# ADDINBRD_V1.net
KiCad netlist of a schematic drawn in EAGLE
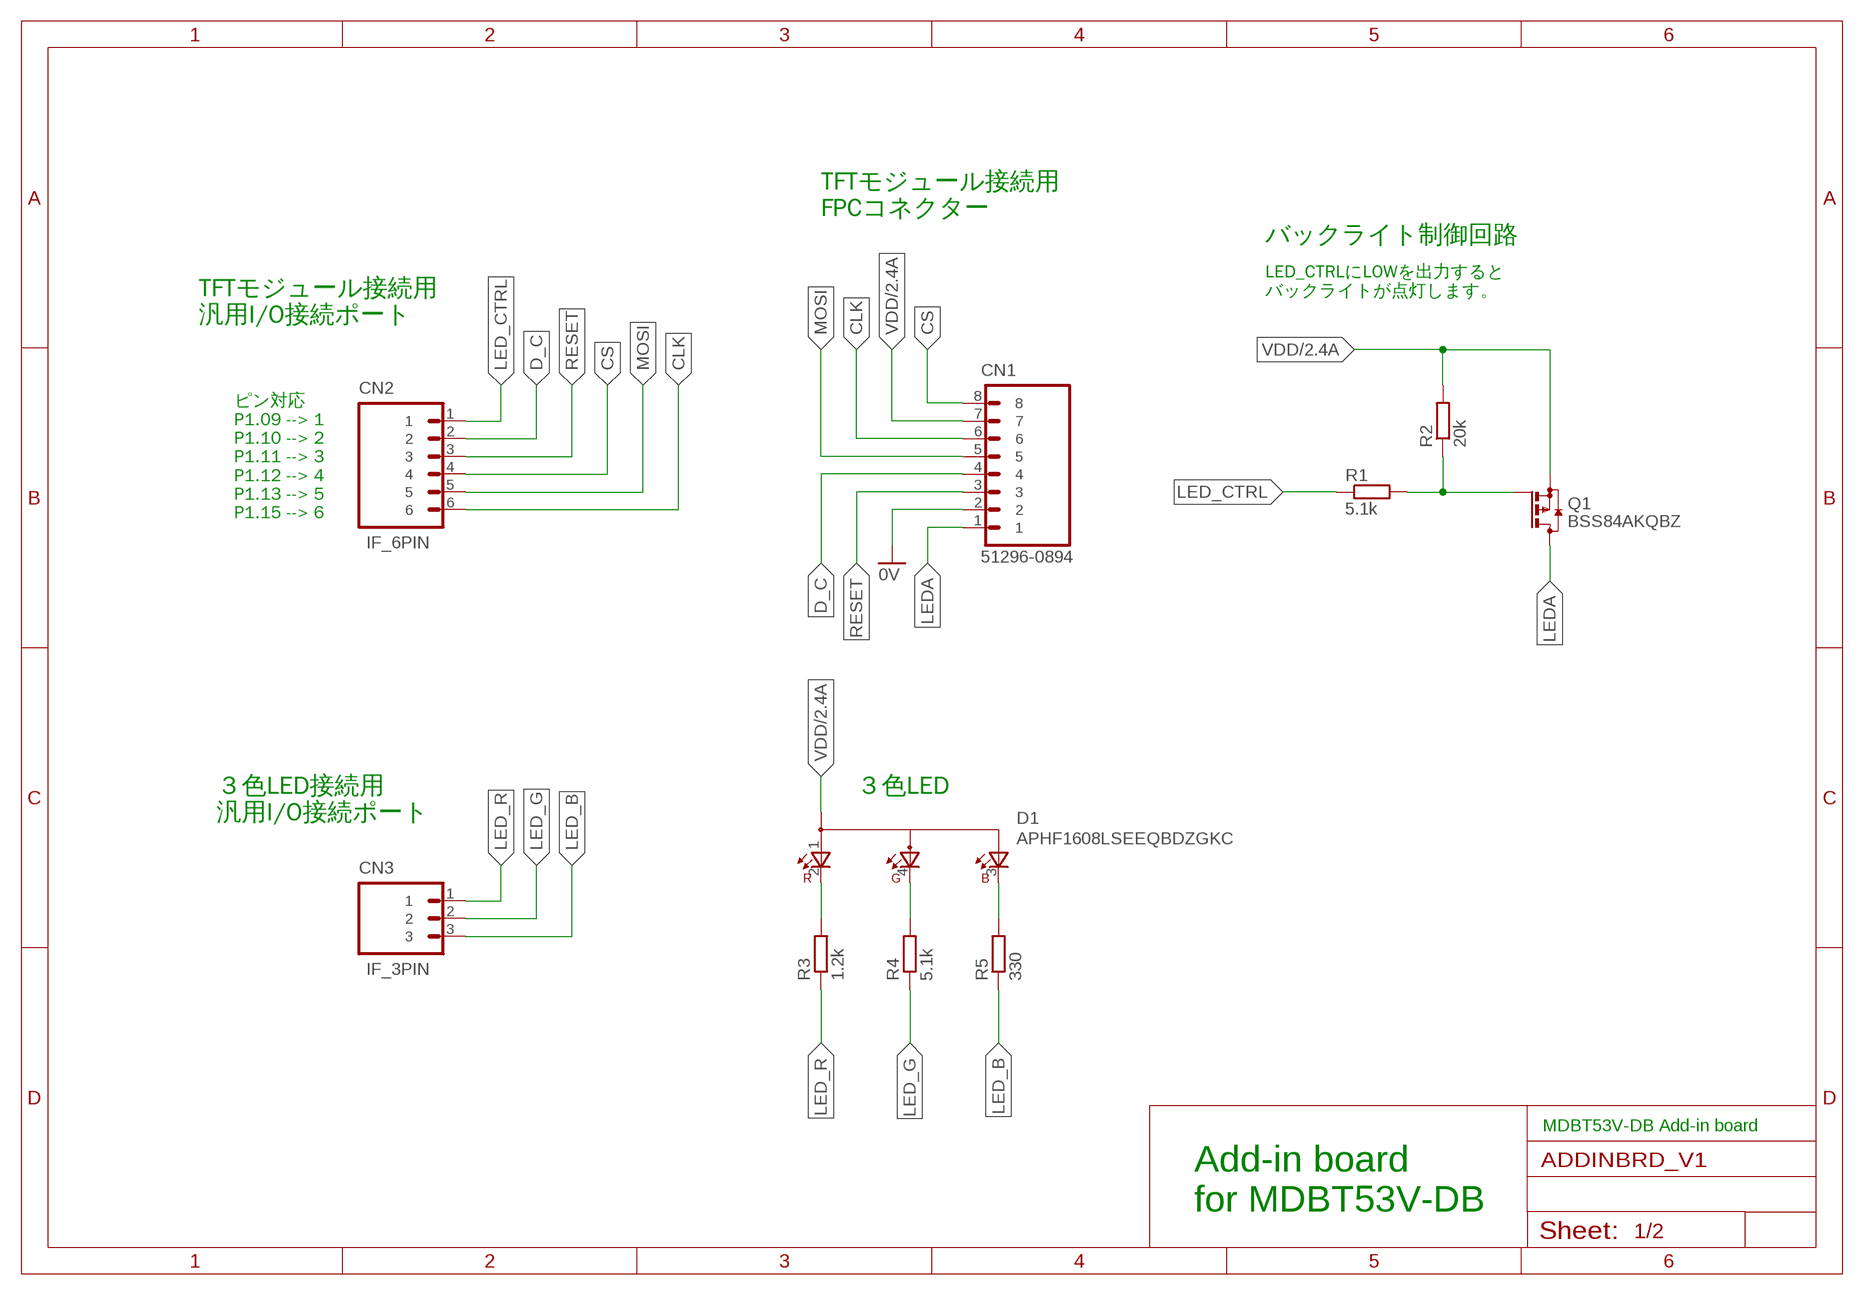
[diagram p0: schematic, sheet 1]
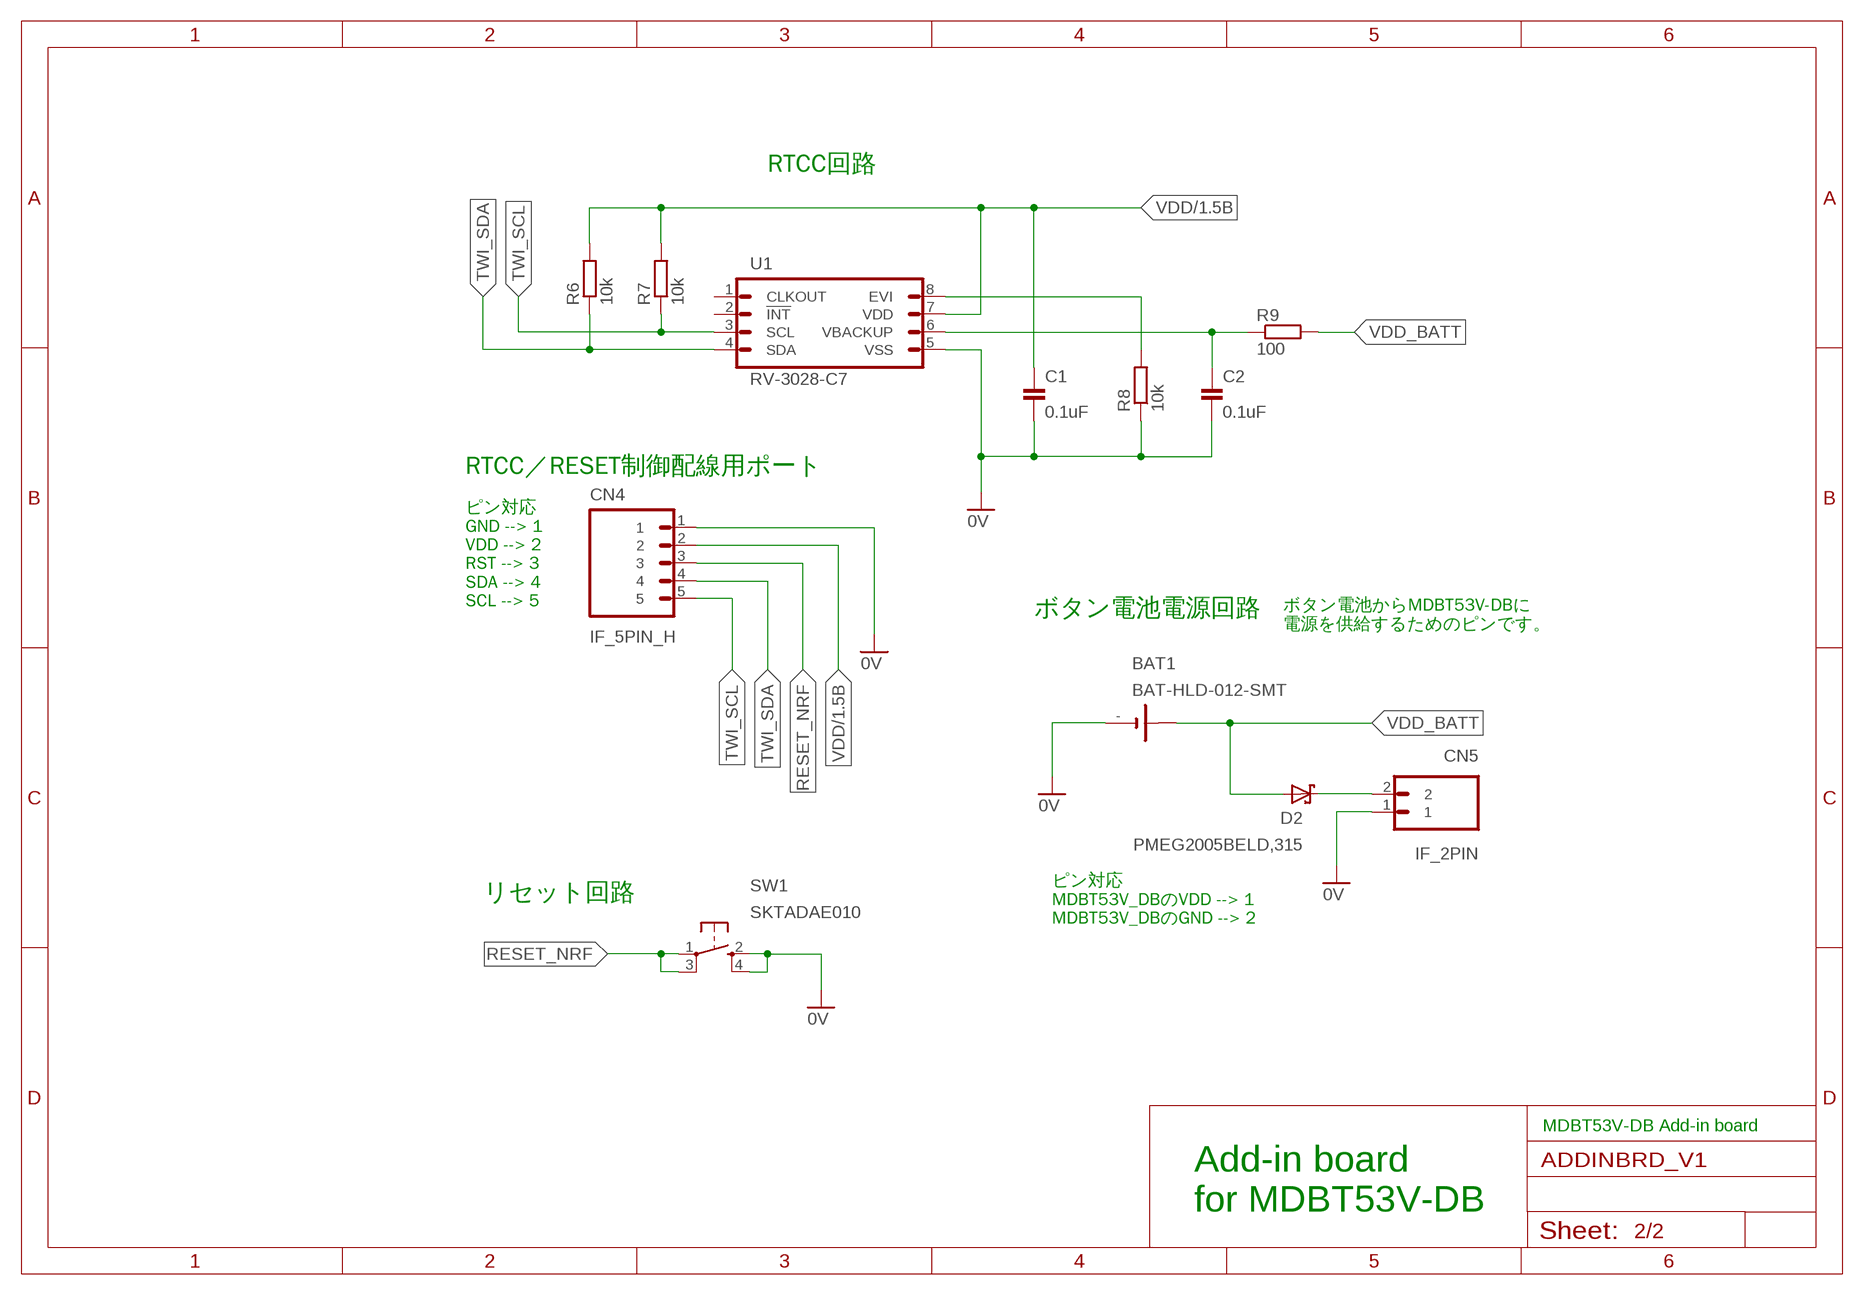
[diagram p1: schematic, sheet 2]

(export (version "E")
  (design (tool "Eeschema 10.0.6"))
  (components
    (comp (ref "CN1")
      (value "51296-0894")
      (footprint "eagle-import:51296-0894")
      (libsource (lib "eagle-import") (part "51296-0894"))
    )
    (comp (ref "CN2")
      (value "IF_6PIN")
      (footprint "eagle-import:HEADER_6PIN")
      (libsource (lib "eagle-import") (part "IF_6PIN"))
    )
    (comp (ref "CN3")
      (value "IF_3PIN")
      (footprint "eagle-import:HEADER_3PIN")
      (libsource (lib "eagle-import") (part "IF_3PIN"))
    )
    (comp (ref "D1")
      (value "APHF1608LSEEQBDZGKC")
      (footprint "eagle-import:APHF1608LSEEQBDZGKC")
      (libsource (lib "eagle-import") (part "APHF1608LSEEQBDZGKC"))
    )
    (comp (ref "Q1")
      (value "BSS84AKQBZ")
      (footprint "eagle-import:BSS84AKQB")
      (libsource (lib "eagle-import") (part "BSS84AKQBZ"))
    )
    (comp (ref "R1")
      (value "5.1k")
      (footprint "eagle-import:R0402N")
      (libsource (lib "eagle-import") (part "RESISTOR_0402N"))
    )
    (comp (ref "R2")
      (value "20k")
      (footprint "eagle-import:R0402N")
      (libsource (lib "eagle-import") (part "RESISTOR_0402N"))
    )
    (comp (ref "R3")
      (value "1.2k")
      (footprint "eagle-import:R0402N")
      (libsource (lib "eagle-import") (part "RESISTOR_0402N"))
    )
    (comp (ref "R4")
      (value "5.1k")
      (footprint "eagle-import:R0402N")
      (libsource (lib "eagle-import") (part "RESISTOR_0402N"))
    )
    (comp (ref "R5")
      (value "330")
      (footprint "eagle-import:R0402N")
      (libsource (lib "eagle-import") (part "RESISTOR_0402N"))
    )
    (comp (ref "BAT1")
      (value "BAT-HLD-012-SMT")
      (footprint "eagle-import:BAT-HLD-012-SMT")
      (libsource (lib "eagle-import") (part "BAT-HLD-012-SMT"))
    )
    (comp (ref "C1")
      (value "0.1uF")
      (footprint "eagle-import:C0402N")
      (libsource (lib "eagle-import") (part "CAP_0402N"))
    )
    (comp (ref "C2")
      (value "0.1uF")
      (footprint "eagle-import:C0402N")
      (libsource (lib "eagle-import") (part "CAP_0402N"))
    )
    (comp (ref "CN4")
      (value "IF_5PIN_H")
      (footprint "eagle-import:HEADER_5PIN")
      (libsource (lib "eagle-import") (part "IF_5PIN_H"))
    )
    (comp (ref "CN5")
      (value "IF_2PIN")
      (footprint "eagle-import:HEADER_2PIN")
      (libsource (lib "eagle-import") (part "IF_2PIN"))
    )
    (comp (ref "D2")
      (value "PMEG2005BELD,315")
      (footprint "eagle-import:DFN1006D-2")
      (libsource (lib "eagle-import") (part "PMEG2005BELD,315"))
    )
    (comp (ref "R6")
      (value "10k")
      (footprint "eagle-import:R0402N")
      (libsource (lib "eagle-import") (part "RESISTOR_0402N"))
    )
    (comp (ref "R7")
      (value "10k")
      (footprint "eagle-import:R0402N")
      (libsource (lib "eagle-import") (part "RESISTOR_0402N"))
    )
    (comp (ref "R8")
      (value "10k")
      (footprint "eagle-import:R0402N")
      (libsource (lib "eagle-import") (part "RESISTOR_0402N"))
    )
    (comp (ref "R9")
      (value "100")
      (footprint "eagle-import:R0402N")
      (libsource (lib "eagle-import") (part "RESISTOR_0402N"))
    )
    (comp (ref "SW1")
      (value "SKTADAE010")
      (footprint "eagle-import:SKTADAE010")
      (libsource (lib "eagle-import") (part "SKTADAE010"))
    )
    (comp (ref "U1")
      (value "RV-3028-C7")
      (footprint "eagle-import:SON-8")
      (libsource (lib "eagle-import") (part "RV-3028-C7"))
    )
  )
  (nets
    (net (code "1") (name "0V") (class "Default")
      (node (ref "BAT1") (pin "-") (pinfunction "-_-") (pintype "passive"))
      (node (ref "C1") (pin "2") (pinfunction "2_2") (pintype "passive"))
      (node (ref "C2") (pin "2") (pinfunction "2_2") (pintype "passive"))
      (node (ref "CN1") (pin "2") (pinfunction "2_2") (pintype "passive"))
      (node (ref "CN4") (pin "1") (pinfunction "1_1") (pintype "passive"))
      (node (ref "CN5") (pin "1") (pinfunction "1_1") (pintype "passive"))
      (node (ref "R8") (pin "1") (pinfunction "1_1") (pintype "passive"))
      (node (ref "SW1") (pin "2") (pinfunction "S_2") (pintype "passive"))
      (node (ref "SW1") (pin "4") (pinfunction "S1_4") (pintype "passive"))
      (node (ref "U1") (pin "5") (pinfunction "VSS_5") (pintype "passive"))
    )
    (net (code "2") (name "CLK") (class "Default")
      (node (ref "CN1") (pin "6") (pinfunction "6_6") (pintype "passive"))
      (node (ref "CN2") (pin "6") (pinfunction "6_6") (pintype "passive"))
    )
    (net (code "3") (name "CS") (class "Default")
      (node (ref "CN1") (pin "8") (pinfunction "8_8") (pintype "passive"))
      (node (ref "CN2") (pin "4") (pinfunction "4_4") (pintype "passive"))
    )
    (net (code "4") (name "D_C") (class "Default")
      (node (ref "CN1") (pin "4") (pinfunction "4_4") (pintype "passive"))
      (node (ref "CN2") (pin "2") (pinfunction "2_2") (pintype "passive"))
    )
    (net (code "5") (name "LEDA") (class "Default")
      (node (ref "CN1") (pin "1") (pinfunction "1_1") (pintype "passive"))
      (node (ref "Q1") (pin "3") (pinfunction "D_3") (pintype "passive"))
    )
    (net (code "6") (name "LED_B") (class "Default")
      (node (ref "CN3") (pin "3") (pinfunction "3_3") (pintype "passive"))
      (node (ref "R5") (pin "1") (pinfunction "1_1") (pintype "passive"))
    )
    (net (code "7") (name "LED_CTRL") (class "Default")
      (node (ref "CN2") (pin "1") (pinfunction "1_1") (pintype "passive"))
      (node (ref "R1") (pin "1") (pinfunction "1_1") (pintype "passive"))
    )
    (net (code "8") (name "LED_G") (class "Default")
      (node (ref "CN3") (pin "2") (pinfunction "2_2") (pintype "passive"))
      (node (ref "R4") (pin "1") (pinfunction "1_1") (pintype "passive"))
    )
    (net (code "9") (name "LED_R") (class "Default")
      (node (ref "CN3") (pin "1") (pinfunction "1_1") (pintype "passive"))
      (node (ref "R3") (pin "1") (pinfunction "1_1") (pintype "passive"))
    )
    (net (code "10") (name "MOSI") (class "Default")
      (node (ref "CN1") (pin "5") (pinfunction "5_5") (pintype "passive"))
      (node (ref "CN2") (pin "5") (pinfunction "5_5") (pintype "passive"))
    )
    (net (code "11") (name "Net-(D1-CBLUE)") (class "Default")
      (node (ref "D1") (pin "3") (pinfunction "CBLUE_3") (pintype "passive"))
      (node (ref "R5") (pin "2") (pinfunction "2_2") (pintype "passive"))
    )
    (net (code "12") (name "Net-(D1-CGREEN)") (class "Default")
      (node (ref "D1") (pin "4") (pinfunction "CGREEN_4") (pintype "passive"))
      (node (ref "R4") (pin "2") (pinfunction "2_2") (pintype "passive"))
    )
    (net (code "13") (name "Net-(D1-CRED)") (class "Default")
      (node (ref "D1") (pin "2") (pinfunction "CRED_2") (pintype "passive"))
      (node (ref "R3") (pin "2") (pinfunction "2_2") (pintype "passive"))
    )
    (net (code "14") (name "Net-(D2-C)") (class "Default")
      (node (ref "CN5") (pin "2") (pinfunction "2_2") (pintype "passive"))
      (node (ref "D2") (pin "1") (pinfunction "C_1") (pintype "passive"))
    )
    (net (code "15") (name "Net-(Q1-G)") (class "Default")
      (node (ref "Q1") (pin "1") (pinfunction "G_1") (pintype "passive"))
      (node (ref "R1") (pin "2") (pinfunction "2_2") (pintype "passive"))
      (node (ref "R2") (pin "1") (pinfunction "1_1") (pintype "passive"))
    )
    (net (code "16") (name "Net-(U1-EVI)") (class "Default")
      (node (ref "R8") (pin "2") (pinfunction "2_2") (pintype "passive"))
      (node (ref "U1") (pin "8") (pinfunction "EVI_8") (pintype "bidirectional"))
    )
    (net (code "17") (name "Net-(U1-VBACKUP)") (class "Default")
      (node (ref "C2") (pin "1") (pinfunction "1_1") (pintype "passive"))
      (node (ref "R9") (pin "1") (pinfunction "1_1") (pintype "passive"))
      (node (ref "U1") (pin "6") (pinfunction "VBACKUP_6") (pintype "passive"))
    )
    (net (code "18") (name "RESET") (class "Default")
      (node (ref "CN1") (pin "3") (pinfunction "3_3") (pintype "passive"))
      (node (ref "CN2") (pin "3") (pinfunction "3_3") (pintype "passive"))
    )
    (net (code "19") (name "RESET_NRF") (class "Default")
      (node (ref "CN4") (pin "3") (pinfunction "3_3") (pintype "passive"))
      (node (ref "SW1") (pin "1") (pinfunction "P_1") (pintype "passive"))
      (node (ref "SW1") (pin "3") (pinfunction "P1_3") (pintype "passive"))
    )
    (net (code "20") (name "TWI_SCL") (class "Default")
      (node (ref "CN4") (pin "5") (pinfunction "5_5") (pintype "passive"))
      (node (ref "R7") (pin "1") (pinfunction "1_1") (pintype "passive"))
      (node (ref "U1") (pin "3") (pinfunction "SCL_3") (pintype "bidirectional"))
    )
    (net (code "21") (name "TWI_SDA") (class "Default")
      (node (ref "CN4") (pin "4") (pinfunction "4_4") (pintype "passive"))
      (node (ref "R6") (pin "1") (pinfunction "1_1") (pintype "passive"))
      (node (ref "U1") (pin "4") (pinfunction "SDA_4") (pintype "bidirectional"))
    )
    (net (code "22") (name "VDD") (class "Default")
      (node (ref "C1") (pin "1") (pinfunction "1_1") (pintype "passive"))
      (node (ref "CN1") (pin "7") (pinfunction "7_7") (pintype "passive"))
      (node (ref "CN4") (pin "2") (pinfunction "2_2") (pintype "passive"))
      (node (ref "D1") (pin "1") (pinfunction "A_1") (pintype "passive"))
      (node (ref "Q1") (pin "2") (pinfunction "S_2") (pintype "passive"))
      (node (ref "R2") (pin "2") (pinfunction "2_2") (pintype "passive"))
      (node (ref "R6") (pin "2") (pinfunction "2_2") (pintype "passive"))
      (node (ref "R7") (pin "2") (pinfunction "2_2") (pintype "passive"))
      (node (ref "U1") (pin "7") (pinfunction "VDD_7") (pintype "passive"))
    )
    (net (code "23") (name "VDD_BATT") (class "Default")
      (node (ref "BAT1") (pin "+@2") (pinfunction "+_+@2") (pintype "passive"))
      (node (ref "D2") (pin "2") (pinfunction "A_2") (pintype "passive"))
      (node (ref "R9") (pin "2") (pinfunction "2_2") (pintype "passive"))
    )
    (net (code "24") (name "unconnected-(U1-CLKOUT-Pad1)") (class "Default")
      (node (ref "U1") (pin "1") (pinfunction "CLKOUT_1") (pintype "bidirectional"))
    )
    (net (code "25") (name "unconnected-(U1-~{INT}-Pad2)") (class "Default")
      (node (ref "U1") (pin "2") (pinfunction "~{INT}_2") (pintype "bidirectional"))
    )
  )
)
